# Sheet1_MCU.net
KiCad netlist of a schematic drawn in Altium Designer
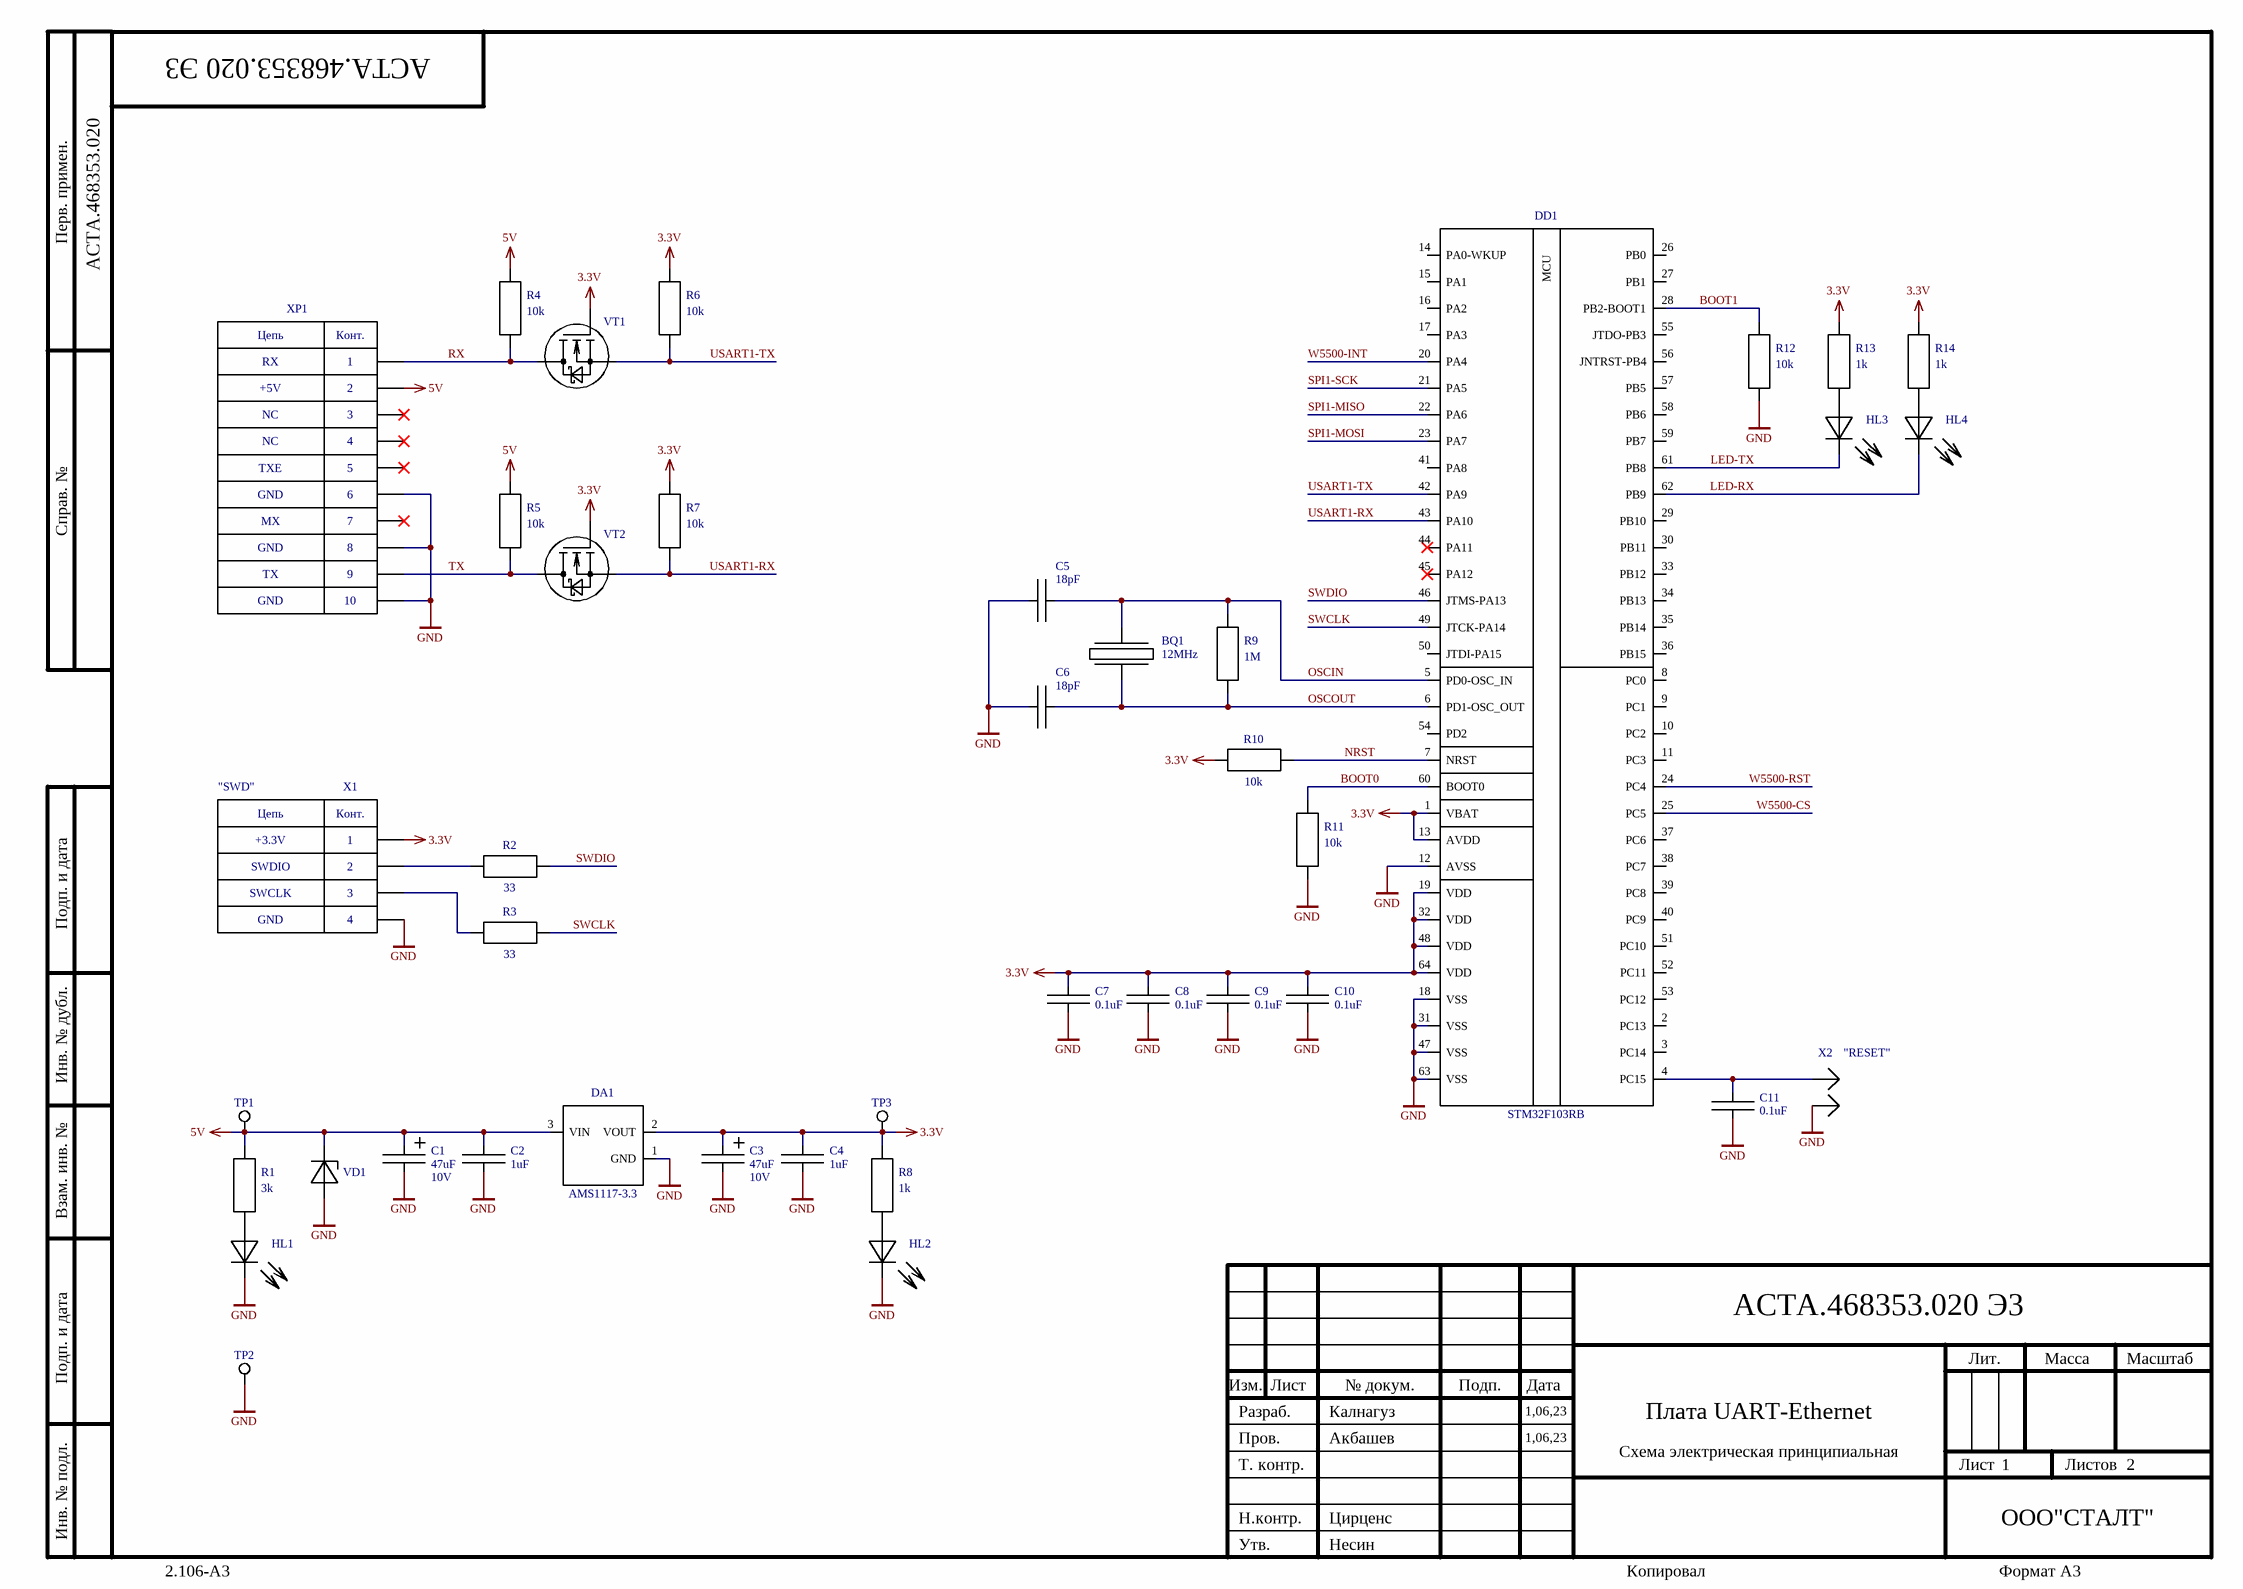
[diagram p0: Sheet1_MCU.SchDoc]

(export (version "E")
  (design (tool "Eeschema 10.0.6"))
  (components
    (comp (ref "BQ1")
      (value "12MHz")
      (footprint "HT-49S")
      (fields (field (name "Comment") "HT-49S_Rated"))
      (libsource (lib "Resonators") (part "HT-49S_Rated"))
    )
    (comp (ref "C1")
      (value "47uF")
      (footprint "CaseB_TantalumCap")
      (fields (field (name "VOLTAGE") "10V") (field (name "Comment") "CaseB_TantalumCap"))
      (libsource (lib "Tantalum_Capacitors") (part "CaseB_TantalumCap"))
    )
    (comp (ref "C2")
      (value "1uF")
      (footprint "CAP0805")
      (fields (field (name "Comment") "CAP0805_Rated"))
      (libsource (lib "Ceramic_Capacitors") (part "CAP0805_Rated"))
    )
    (comp (ref "C3")
      (value "47uF")
      (footprint "CaseB_TantalumCap")
      (fields (field (name "VOLTAGE") "10V") (field (name "Comment") "CaseB_TantalumCap"))
      (libsource (lib "Tantalum_Capacitors") (part "CaseB_TantalumCap"))
    )
    (comp (ref "C4")
      (value "1uF")
      (footprint "CAP0805")
      (fields (field (name "Comment") "CAP0805_Rated"))
      (libsource (lib "Ceramic_Capacitors") (part "CAP0805_Rated"))
    )
    (comp (ref "C5")
      (value "18pF")
      (footprint "CAP0805")
      (fields (field (name "Comment") "CAP0805_Rated"))
      (libsource (lib "Ceramic_Capacitors") (part "CAP0805_Rated"))
    )
    (comp (ref "C6")
      (value "18pF")
      (footprint "CAP0805")
      (fields (field (name "Comment") "CAP0805_Rated"))
      (libsource (lib "Ceramic_Capacitors") (part "CAP0805_Rated"))
    )
    (comp (ref "C7")
      (value "0.1uF")
      (footprint "CAP0805")
      (fields (field (name "Comment") "CAP0805_Rated"))
      (libsource (lib "Ceramic_Capacitors") (part "CAP0805_Rated"))
    )
    (comp (ref "C8")
      (value "0.1uF")
      (footprint "CAP0805")
      (fields (field (name "Comment") "CAP0805_Rated"))
      (libsource (lib "Ceramic_Capacitors") (part "CAP0805_Rated"))
    )
    (comp (ref "C9")
      (value "0.1uF")
      (footprint "CAP0805")
      (fields (field (name "Comment") "CAP0805_Rated"))
      (libsource (lib "Ceramic_Capacitors") (part "CAP0805_Rated"))
    )
    (comp (ref "C10")
      (value "0.1uF")
      (footprint "CAP0805")
      (fields (field (name "Comment") "CAP0805_Rated"))
      (libsource (lib "Ceramic_Capacitors") (part "CAP0805_Rated"))
    )
    (comp (ref "C11")
      (value "0.1uF")
      (footprint "CAP0805")
      (fields (field (name "Comment") "CAP0805_Rated"))
      (libsource (lib "Ceramic_Capacitors") (part "CAP0805_Rated"))
    )
    (comp (ref "DA1")
      (value "AMS1117-3.3")
      (footprint "SOT-223")
      (description "Fixed Voltage 3.3V 1A Low Dropout Voltage Regulator")
      (libsource (lib "Power_Management_ICs") (part "AMS1117-3.3"))
    )
    (comp (ref "DD1")
      (value "STM32F103RB")
      (footprint "LQFP-64")
      (description "ARM Cortex-M3 MCU")
      (libsource (lib "MCU") (part "STM32F103RB"))
    )
    (comp (ref "HL1")
      (value "KPTD-3216MGC")
      (footprint "KPTD-3216 Green")
      (description "3.2x1.6mm SMD LED Mega Green")
      (libsource (lib "LEDs_SMD") (part "KPTD-3216MGC"))
    )
    (comp (ref "HL2")
      (value "KPTD-3216MGC")
      (footprint "KPTD-3216 Green")
      (description "3.2x1.6mm SMD LED Mega Green")
      (libsource (lib "LEDs_SMD") (part "KPTD-3216MGC"))
    )
    (comp (ref "HL3")
      (value "KPTD-3216MGC")
      (footprint "KPTD-3216 Green")
      (description "3.2x1.6mm SMD LED Mega Green")
      (libsource (lib "LEDs_SMD") (part "KPTD-3216MGC"))
    )
    (comp (ref "HL4")
      (value "KPTD-3216SYC")
      (footprint "KPTD-3216 Yellow")
      (description "3.2x1.6mm SMD LED Super Bright Yellow")
      (libsource (lib "LEDs_SMD") (part "KPTD-3216SYC"))
    )
    (comp (ref "R1")
      (value "3k")
      (footprint "RES0805")
      (fields (field (name "TOLERANCE") "5%") (field (name "Comment") "RES0805_Rated"))
      (libsource (lib "Resistors") (part "RES0805_Rated"))
    )
    (comp (ref "R2")
      (value "33")
      (footprint "RES0805")
      (fields (field (name "TOLERANCE") "5%") (field (name "Comment") "RES0805_Rated"))
      (libsource (lib "") (part "RES0805_Rated_1"))
    )
    (comp (ref "R3")
      (value "33")
      (footprint "RES0805")
      (fields (field (name "TOLERANCE") "5%") (field (name "Comment") "RES0805_Rated"))
      (libsource (lib "") (part "RES0805_Rated_1"))
    )
    (comp (ref "R4")
      (value "10k")
      (footprint "RES0805")
      (fields (field (name "TOLERANCE") "5%") (field (name "Comment") "RES0805_Rated"))
      (libsource (lib "Resistors") (part "RES0805_Rated"))
    )
    (comp (ref "R5")
      (value "10k")
      (footprint "RES0805")
      (fields (field (name "TOLERANCE") "5%") (field (name "Comment") "RES0805_Rated"))
      (libsource (lib "Resistors") (part "RES0805_Rated"))
    )
    (comp (ref "R6")
      (value "10k")
      (footprint "RES0805")
      (fields (field (name "TOLERANCE") "5%") (field (name "Comment") "RES0805_Rated"))
      (libsource (lib "Resistors") (part "RES0805_Rated"))
    )
    (comp (ref "R7")
      (value "10k")
      (footprint "RES0805")
      (fields (field (name "TOLERANCE") "5%") (field (name "Comment") "RES0805_Rated"))
      (libsource (lib "Resistors") (part "RES0805_Rated"))
    )
    (comp (ref "R8")
      (value "1k")
      (footprint "RES0805")
      (fields (field (name "TOLERANCE") "5%") (field (name "Comment") "RES0805_Rated"))
      (libsource (lib "Resistors") (part "RES0805_Rated"))
    )
    (comp (ref "R9")
      (value "1M")
      (footprint "RES0805")
      (fields (field (name "TOLERANCE") "5%") (field (name "Comment") "RES0805_Rated"))
      (libsource (lib "Resistors") (part "RES0805_Rated"))
    )
    (comp (ref "R10")
      (value "10k")
      (footprint "RES0805")
      (fields (field (name "TOLERANCE") "5%") (field (name "Comment") "RES0805_Rated"))
      (libsource (lib "") (part "RES0805_Rated_1"))
    )
    (comp (ref "R11")
      (value "10k")
      (footprint "RES0805")
      (fields (field (name "TOLERANCE") "5%") (field (name "Comment") "RES0805_Rated"))
      (libsource (lib "Resistors") (part "RES0805_Rated"))
    )
    (comp (ref "R12")
      (value "10k")
      (footprint "RES0805")
      (fields (field (name "TOLERANCE") "5%") (field (name "Comment") "RES0805_Rated"))
      (libsource (lib "Resistors") (part "RES0805_Rated"))
    )
    (comp (ref "R13")
      (value "1k")
      (footprint "RES0805")
      (fields (field (name "TOLERANCE") "5%") (field (name "Comment") "RES0805_Rated"))
      (libsource (lib "Resistors") (part "RES0805_Rated"))
    )
    (comp (ref "R14")
      (value "1k")
      (footprint "RES0805")
      (fields (field (name "TOLERANCE") "5%") (field (name "Comment") "RES0805_Rated"))
      (libsource (lib "Resistors") (part "RES0805_Rated"))
    )
    (comp (ref "TP1")
      (value "TestPad")
      (footprint "PAD-TH-OCT1x1-0.5")
      (description "TestPoint on PCB")
      (libsource (lib "Connectors") (part "TestPad"))
    )
    (comp (ref "TP2")
      (value "TestPad")
      (footprint "PAD-TH-OCT1x1-0.5")
      (description "TestPoint on PCB")
      (libsource (lib "Connectors") (part "TestPad"))
    )
    (comp (ref "TP3")
      (value "TestPad")
      (footprint "PAD-TH-OCT1x1-0.5")
      (description "TestPoint on PCB")
      (libsource (lib "Connectors") (part "TestPad"))
    )
    (comp (ref "VD1")
      (value "SMAJ5.0A")
      (footprint "SMA (DO-214AC)")
      (description "5Vr 400W 43.5A UniDirectional TVS")
      (libsource (lib "TVS_Diodes") (part "SMAJ5.0A"))
    )
    (comp (ref "VT1")
      (value "BSS138")
      (footprint "SOT-23")
      (description "Small Signal N-Channel MOSFET 50V 220mA")
      (libsource (lib "MOSFETs") (part "BSS138"))
    )
    (comp (ref "VT2")
      (value "BSS138")
      (footprint "SOT-23")
      (description "Small Signal N-Channel MOSFET 50V 220mA")
      (libsource (lib "MOSFETs") (part "BSS138"))
    )
    (comp (ref "X1")
      (value "PBS-4")
      (footprint "PBS-4")
      (description "Female Header Pitch 2.54mm")
      (fields
        (field (name "CIRCUIT4") "GND")
        (field (name "CIRCUIT3") "SWCLK")
        (field (name "CIRCUIT1") "+3.3V")
        (field (name "CIRCUIT2") "SWDIO")
        (field (name "LABEL") "\"SWD\"")
      )
      (libsource (lib "Connectors") (part "PBS-4"))
    )
    (comp (ref "X2")
      (value "PLS-2")
      (footprint "PLS-2")
      (description "Pin Header Pitch 2.54mm")
      (fields (field (name "LABEL") "\"RESET\""))
      (libsource (lib "Connectors") (part "PLS-2"))
    )
    (comp (ref "XP1")
      (value "IDC-10MS")
      (footprint "IDC-10MS pad1.6x2.0")
      (description "Box Header Pitch 2.54mm")
      (fields
        (field (name "CIRCUIT7") "MX")
        (field (name "CIRCUIT8") "GND")
        (field (name "CIRCUIT9") "TX")
        (field (name "CIRCUIT10") "GND")
        (field (name "CIRCUIT6") "GND")
        (field (name "CIRCUIT4") "NC")
        (field (name "CIRCUIT5") "TXE")
        (field (name "CIRCUIT3") "NC")
        (field (name "CIRCUIT2") "+5V")
        (field (name "CIRCUIT1") "RX")
      )
      (libsource (lib "Connectors") (part "IDC-10MS"))
    )
  )
  (nets
    (net (code "1") (name "/BOOT0") (class "Default")
      (node (ref "DD1") (pin "60") (pinfunction "BOOT0_60") (pintype "power_in"))
      (node (ref "R11") (pin "2") (pinfunction "2_2") (pintype "passive"))
    )
    (net (code "2") (name "/BOOT1") (class "Default")
      (node (ref "DD1") (pin "28") (pinfunction "PB2-BOOT1_28") (pintype "bidirectional"))
      (node (ref "R12") (pin "2") (pinfunction "2_2") (pintype "passive"))
    )
    (net (code "3") (name "/LED-RX") (class "Default")
      (node (ref "DD1") (pin "62") (pinfunction "PB9_62") (pintype "bidirectional"))
      (node (ref "HL4") (pin "K") (pinfunction "K_K") (pintype "passive"))
    )
    (net (code "4") (name "/LED-TX") (class "Default")
      (node (ref "DD1") (pin "61") (pinfunction "PB8_61") (pintype "bidirectional"))
      (node (ref "HL3") (pin "K") (pinfunction "K_K") (pintype "passive"))
    )
    (net (code "5") (name "/NRST") (class "Default")
      (node (ref "DD1") (pin "7") (pinfunction "NRST_7") (pintype "bidirectional"))
      (node (ref "R10") (pin "2") (pinfunction "2_2") (pintype "passive"))
    )
    (net (code "6") (name "/OSCIN") (class "Default")
      (node (ref "BQ1") (pin "1") (pinfunction "1_1") (pintype "passive"))
      (node (ref "C5") (pin "2") (pinfunction "2_2") (pintype "passive"))
      (node (ref "DD1") (pin "5") (pinfunction "PD0-OSC_IN_5") (pintype "bidirectional"))
      (node (ref "R9") (pin "2") (pinfunction "2_2") (pintype "passive"))
    )
    (net (code "7") (name "/OSCOUT") (class "Default")
      (node (ref "BQ1") (pin "2") (pinfunction "2_2") (pintype "passive"))
      (node (ref "C6") (pin "2") (pinfunction "2_2") (pintype "passive"))
      (node (ref "DD1") (pin "6") (pinfunction "PD1-OSC_OUT_6") (pintype "bidirectional"))
      (node (ref "R9") (pin "1") (pinfunction "1_1") (pintype "passive"))
    )
    (net (code "8") (name "/RX") (class "Default")
      (node (ref "R4") (pin "1") (pinfunction "1_1") (pintype "passive"))
      (node (ref "VT1") (pin "2") (pinfunction "D_2") (pintype "passive"))
      (node (ref "XP1") (pin "1") (pinfunction "1_1") (pintype "passive"))
    )
    (net (code "9") (name "/SPI1-MISO") (class "Default")
      (node (ref "DD1") (pin "22") (pinfunction "PA6_22") (pintype "bidirectional"))
    )
    (net (code "10") (name "/SPI1-MOSI") (class "Default")
      (node (ref "DD1") (pin "23") (pinfunction "PA7_23") (pintype "bidirectional"))
    )
    (net (code "11") (name "/SPI1-SCK") (class "Default")
      (node (ref "DD1") (pin "21") (pinfunction "PA5_21") (pintype "bidirectional"))
    )
    (net (code "12") (name "/SWCLK") (class "Default")
      (node (ref "DD1") (pin "49") (pinfunction "JTCK-PA14_49") (pintype "bidirectional"))
      (node (ref "R3") (pin "2") (pinfunction "2_2") (pintype "passive"))
    )
    (net (code "13") (name "/SWDIO") (class "Default")
      (node (ref "DD1") (pin "46") (pinfunction "JTMS-PA13_46") (pintype "bidirectional"))
      (node (ref "R2") (pin "2") (pinfunction "2_2") (pintype "passive"))
    )
    (net (code "14") (name "/TX") (class "Default")
      (node (ref "R5") (pin "1") (pinfunction "1_1") (pintype "passive"))
      (node (ref "VT2") (pin "2") (pinfunction "D_2") (pintype "passive"))
      (node (ref "XP1") (pin "9") (pinfunction "9_9") (pintype "passive"))
    )
    (net (code "15") (name "/USART1-RX") (class "Default")
      (node (ref "DD1") (pin "43") (pinfunction "PA10_43") (pintype "bidirectional"))
      (node (ref "R7") (pin "1") (pinfunction "1_1") (pintype "passive"))
      (node (ref "VT2") (pin "3") (pinfunction "S_3") (pintype "passive"))
    )
    (net (code "16") (name "/USART1-TX") (class "Default")
      (node (ref "DD1") (pin "42") (pinfunction "PA9_42") (pintype "bidirectional"))
      (node (ref "R6") (pin "1") (pinfunction "1_1") (pintype "passive"))
      (node (ref "VT1") (pin "3") (pinfunction "S_3") (pintype "passive"))
    )
    (net (code "17") (name "/W5500-CS") (class "Default")
      (node (ref "DD1") (pin "25") (pinfunction "PC5_25") (pintype "bidirectional"))
    )
    (net (code "18") (name "/W5500-INT") (class "Default")
      (node (ref "DD1") (pin "20") (pinfunction "PA4_20") (pintype "bidirectional"))
    )
    (net (code "19") (name "/W5500-RST") (class "Default")
      (node (ref "DD1") (pin "24") (pinfunction "PC4_24") (pintype "bidirectional"))
    )
    (net (code "20") (name "3.3V") (class "Default")
      (node (ref "C10") (pin "1") (pinfunction "1_1") (pintype "passive"))
      (node (ref "C3") (pin "1") (pinfunction "+_1") (pintype "passive"))
      (node (ref "C4") (pin "1") (pinfunction "1_1") (pintype "passive"))
      (node (ref "C7") (pin "1") (pinfunction "1_1") (pintype "passive"))
      (node (ref "C8") (pin "1") (pinfunction "1_1") (pintype "passive"))
      (node (ref "C9") (pin "1") (pinfunction "1_1") (pintype "passive"))
      (node (ref "DA1") (pin "2") (pinfunction "VOUT_2") (pintype "power_in"))
      (node (ref "DD1") (pin "1") (pinfunction "VBAT_1") (pintype "power_in"))
      (node (ref "DD1") (pin "13") (pinfunction "AVDD_13") (pintype "power_in"))
      (node (ref "DD1") (pin "19") (pinfunction "VDD_19") (pintype "power_in"))
      (node (ref "DD1") (pin "32") (pinfunction "VDD_32") (pintype "power_in"))
      (node (ref "DD1") (pin "48") (pinfunction "VDD_48") (pintype "power_in"))
      (node (ref "DD1") (pin "64") (pinfunction "VDD_64") (pintype "power_in"))
      (node (ref "R10") (pin "1") (pinfunction "1_1") (pintype "passive"))
      (node (ref "R13") (pin "2") (pinfunction "2_2") (pintype "passive"))
      (node (ref "R14") (pin "2") (pinfunction "2_2") (pintype "passive"))
      (node (ref "R6") (pin "2") (pinfunction "2_2") (pintype "passive"))
      (node (ref "R7") (pin "2") (pinfunction "2_2") (pintype "passive"))
      (node (ref "R8") (pin "2") (pinfunction "2_2") (pintype "passive"))
      (node (ref "TP3") (pin "1") (pinfunction "1_1") (pintype "passive"))
      (node (ref "VT1") (pin "1") (pinfunction "G_1") (pintype "passive"))
      (node (ref "VT2") (pin "1") (pinfunction "G_1") (pintype "passive"))
      (node (ref "X1") (pin "1") (pinfunction "1_1") (pintype "passive"))
    )
    (net (code "21") (name "5V") (class "Default")
      (node (ref "C1") (pin "1") (pinfunction "+_1") (pintype "passive"))
      (node (ref "C2") (pin "1") (pinfunction "1_1") (pintype "passive"))
      (node (ref "DA1") (pin "3") (pinfunction "VIN_3") (pintype "power_in"))
      (node (ref "R1") (pin "2") (pinfunction "2_2") (pintype "passive"))
      (node (ref "R4") (pin "2") (pinfunction "2_2") (pintype "passive"))
      (node (ref "R5") (pin "2") (pinfunction "2_2") (pintype "passive"))
      (node (ref "TP1") (pin "1") (pinfunction "1_1") (pintype "passive"))
      (node (ref "VD1") (pin "K") (pinfunction "K_K") (pintype "passive"))
      (node (ref "XP1") (pin "2") (pinfunction "2_2") (pintype "passive"))
    )
    (net (code "22") (name "GND") (class "Default")
      (node (ref "C1") (pin "2") (pinfunction "-_2") (pintype "passive"))
      (node (ref "C10") (pin "2") (pinfunction "2_2") (pintype "passive"))
      (node (ref "C11") (pin "2") (pinfunction "2_2") (pintype "passive"))
      (node (ref "C2") (pin "2") (pinfunction "2_2") (pintype "passive"))
      (node (ref "C3") (pin "2") (pinfunction "-_2") (pintype "passive"))
      (node (ref "C4") (pin "2") (pinfunction "2_2") (pintype "passive"))
      (node (ref "C5") (pin "1") (pinfunction "1_1") (pintype "passive"))
      (node (ref "C6") (pin "1") (pinfunction "1_1") (pintype "passive"))
      (node (ref "C7") (pin "2") (pinfunction "2_2") (pintype "passive"))
      (node (ref "C8") (pin "2") (pinfunction "2_2") (pintype "passive"))
      (node (ref "C9") (pin "2") (pinfunction "2_2") (pintype "passive"))
      (node (ref "DA1") (pin "1") (pinfunction "GND_1") (pintype "power_in"))
      (node (ref "DD1") (pin "12") (pinfunction "AVSS_12") (pintype "power_in"))
      (node (ref "DD1") (pin "18") (pinfunction "VSS_18") (pintype "power_in"))
      (node (ref "DD1") (pin "31") (pinfunction "VSS_31") (pintype "power_in"))
      (node (ref "DD1") (pin "47") (pinfunction "VSS_47") (pintype "power_in"))
      (node (ref "DD1") (pin "63") (pinfunction "VSS_63") (pintype "power_in"))
      (node (ref "HL1") (pin "K") (pinfunction "K_K") (pintype "passive"))
      (node (ref "HL2") (pin "K") (pinfunction "K_K") (pintype "passive"))
      (node (ref "R11") (pin "1") (pinfunction "1_1") (pintype "passive"))
      (node (ref "R12") (pin "1") (pinfunction "1_1") (pintype "passive"))
      (node (ref "TP2") (pin "1") (pinfunction "1_1") (pintype "passive"))
      (node (ref "VD1") (pin "A") (pinfunction "A_A") (pintype "passive"))
      (node (ref "X1") (pin "4") (pinfunction "4_4") (pintype "passive"))
      (node (ref "X2") (pin "2") (pinfunction "2_2") (pintype "passive"))
      (node (ref "XP1") (pin "10") (pinfunction "10_10") (pintype "passive"))
      (node (ref "XP1") (pin "6") (pinfunction "6_6") (pintype "passive"))
      (node (ref "XP1") (pin "8") (pinfunction "8_8") (pintype "passive"))
    )
    (net (code "23") (name "Net-(DD1-PC15)") (class "Default")
      (node (ref "C11") (pin "1") (pinfunction "1_1") (pintype "passive"))
      (node (ref "DD1") (pin "4") (pinfunction "PC15_4") (pintype "bidirectional"))
      (node (ref "X2") (pin "1") (pinfunction "1_1") (pintype "passive"))
    )
    (net (code "24") (name "Net-(HL1-PadA)") (class "Default")
      (node (ref "HL1") (pin "A") (pinfunction "A_A") (pintype "passive"))
      (node (ref "R1") (pin "1") (pinfunction "1_1") (pintype "passive"))
    )
    (net (code "25") (name "Net-(HL2-PadA)") (class "Default")
      (node (ref "HL2") (pin "A") (pinfunction "A_A") (pintype "passive"))
      (node (ref "R8") (pin "1") (pinfunction "1_1") (pintype "passive"))
    )
    (net (code "26") (name "Net-(HL3-PadA)") (class "Default")
      (node (ref "HL3") (pin "A") (pinfunction "A_A") (pintype "passive"))
      (node (ref "R13") (pin "1") (pinfunction "1_1") (pintype "passive"))
    )
    (net (code "27") (name "Net-(HL4-PadA)") (class "Default")
      (node (ref "HL4") (pin "A") (pinfunction "A_A") (pintype "passive"))
      (node (ref "R14") (pin "1") (pinfunction "1_1") (pintype "passive"))
    )
    (net (code "28") (name "Net-(R2-Pad1)") (class "Default")
      (node (ref "R2") (pin "1") (pinfunction "1_1") (pintype "passive"))
      (node (ref "X1") (pin "2") (pinfunction "2_2") (pintype "passive"))
    )
    (net (code "29") (name "Net-(R3-Pad1)") (class "Default")
      (node (ref "R3") (pin "1") (pinfunction "1_1") (pintype "passive"))
      (node (ref "X1") (pin "3") (pinfunction "3_3") (pintype "passive"))
    )
    (net (code "30") (name "unconnected-(DD1-JNTRST-PB4-Pad56)") (class "Default")
      (node (ref "DD1") (pin "56") (pinfunction "JNTRST-PB4_56") (pintype "bidirectional"))
    )
    (net (code "31") (name "unconnected-(DD1-JTDI-PA15-Pad50)") (class "Default")
      (node (ref "DD1") (pin "50") (pinfunction "JTDI-PA15_50") (pintype "bidirectional"))
    )
    (net (code "32") (name "unconnected-(DD1-JTDO-PB3-Pad55)") (class "Default")
      (node (ref "DD1") (pin "55") (pinfunction "JTDO-PB3_55") (pintype "bidirectional"))
    )
    (net (code "33") (name "unconnected-(DD1-PA0-WKUP-Pad14)") (class "Default")
      (node (ref "DD1") (pin "14") (pinfunction "PA0-WKUP_14") (pintype "bidirectional"))
    )
    (net (code "34") (name "unconnected-(DD1-PA1-Pad15)") (class "Default")
      (node (ref "DD1") (pin "15") (pinfunction "PA1_15") (pintype "bidirectional"))
    )
    (net (code "35") (name "unconnected-(DD1-PA2-Pad16)") (class "Default")
      (node (ref "DD1") (pin "16") (pinfunction "PA2_16") (pintype "bidirectional"))
    )
    (net (code "36") (name "unconnected-(DD1-PA3-Pad17)") (class "Default")
      (node (ref "DD1") (pin "17") (pinfunction "PA3_17") (pintype "bidirectional"))
    )
    (net (code "37") (name "unconnected-(DD1-PA8-Pad41)") (class "Default")
      (node (ref "DD1") (pin "41") (pinfunction "PA8_41") (pintype "bidirectional"))
    )
    (net (code "38") (name "unconnected-(DD1-PA11-Pad44)") (class "Default")
      (node (ref "DD1") (pin "44") (pinfunction "PA11_44") (pintype "bidirectional+no_connect"))
    )
    (net (code "39") (name "unconnected-(DD1-PA12-Pad45)") (class "Default")
      (node (ref "DD1") (pin "45") (pinfunction "PA12_45") (pintype "bidirectional+no_connect"))
    )
    (net (code "40") (name "unconnected-(DD1-PB0-Pad26)") (class "Default")
      (node (ref "DD1") (pin "26") (pinfunction "PB0_26") (pintype "bidirectional"))
    )
    (net (code "41") (name "unconnected-(DD1-PB1-Pad27)") (class "Default")
      (node (ref "DD1") (pin "27") (pinfunction "PB1_27") (pintype "bidirectional"))
    )
    (net (code "42") (name "unconnected-(DD1-PB5-Pad57)") (class "Default")
      (node (ref "DD1") (pin "57") (pinfunction "PB5_57") (pintype "bidirectional"))
    )
    (net (code "43") (name "unconnected-(DD1-PB6-Pad58)") (class "Default")
      (node (ref "DD1") (pin "58") (pinfunction "PB6_58") (pintype "bidirectional"))
    )
    (net (code "44") (name "unconnected-(DD1-PB7-Pad59)") (class "Default")
      (node (ref "DD1") (pin "59") (pinfunction "PB7_59") (pintype "bidirectional"))
    )
    (net (code "45") (name "unconnected-(DD1-PB10-Pad29)") (class "Default")
      (node (ref "DD1") (pin "29") (pinfunction "PB10_29") (pintype "bidirectional"))
    )
    (net (code "46") (name "unconnected-(DD1-PB11-Pad30)") (class "Default")
      (node (ref "DD1") (pin "30") (pinfunction "PB11_30") (pintype "bidirectional"))
    )
    (net (code "47") (name "unconnected-(DD1-PB12-Pad33)") (class "Default")
      (node (ref "DD1") (pin "33") (pinfunction "PB12_33") (pintype "bidirectional"))
    )
    (net (code "48") (name "unconnected-(DD1-PB13-Pad34)") (class "Default")
      (node (ref "DD1") (pin "34") (pinfunction "PB13_34") (pintype "bidirectional"))
    )
    (net (code "49") (name "unconnected-(DD1-PB14-Pad35)") (class "Default")
      (node (ref "DD1") (pin "35") (pinfunction "PB14_35") (pintype "bidirectional"))
    )
    (net (code "50") (name "unconnected-(DD1-PB15-Pad36)") (class "Default")
      (node (ref "DD1") (pin "36") (pinfunction "PB15_36") (pintype "bidirectional"))
    )
    (net (code "51") (name "unconnected-(DD1-PC0-Pad8)") (class "Default")
      (node (ref "DD1") (pin "8") (pinfunction "PC0_8") (pintype "bidirectional"))
    )
    (net (code "52") (name "unconnected-(DD1-PC1-Pad9)") (class "Default")
      (node (ref "DD1") (pin "9") (pinfunction "PC1_9") (pintype "bidirectional"))
    )
    (net (code "53") (name "unconnected-(DD1-PC2-Pad10)") (class "Default")
      (node (ref "DD1") (pin "10") (pinfunction "PC2_10") (pintype "bidirectional"))
    )
    (net (code "54") (name "unconnected-(DD1-PC3-Pad11)") (class "Default")
      (node (ref "DD1") (pin "11") (pinfunction "PC3_11") (pintype "bidirectional"))
    )
    (net (code "55") (name "unconnected-(DD1-PC6-Pad37)") (class "Default")
      (node (ref "DD1") (pin "37") (pinfunction "PC6_37") (pintype "bidirectional"))
    )
    (net (code "56") (name "unconnected-(DD1-PC7-Pad38)") (class "Default")
      (node (ref "DD1") (pin "38") (pinfunction "PC7_38") (pintype "bidirectional"))
    )
    (net (code "57") (name "unconnected-(DD1-PC8-Pad39)") (class "Default")
      (node (ref "DD1") (pin "39") (pinfunction "PC8_39") (pintype "bidirectional"))
    )
    (net (code "58") (name "unconnected-(DD1-PC9-Pad40)") (class "Default")
      (node (ref "DD1") (pin "40") (pinfunction "PC9_40") (pintype "bidirectional"))
    )
    (net (code "59") (name "unconnected-(DD1-PC10-Pad51)") (class "Default")
      (node (ref "DD1") (pin "51") (pinfunction "PC10_51") (pintype "bidirectional"))
    )
    (net (code "60") (name "unconnected-(DD1-PC11-Pad52)") (class "Default")
      (node (ref "DD1") (pin "52") (pinfunction "PC11_52") (pintype "bidirectional"))
    )
    (net (code "61") (name "unconnected-(DD1-PC12-Pad53)") (class "Default")
      (node (ref "DD1") (pin "53") (pinfunction "PC12_53") (pintype "bidirectional"))
    )
    (net (code "62") (name "unconnected-(DD1-PC13-Pad2)") (class "Default")
      (node (ref "DD1") (pin "2") (pinfunction "PC13_2") (pintype "bidirectional"))
    )
    (net (code "63") (name "unconnected-(DD1-PC14-Pad3)") (class "Default")
      (node (ref "DD1") (pin "3") (pinfunction "PC14_3") (pintype "bidirectional"))
    )
    (net (code "64") (name "unconnected-(DD1-PD2-Pad54)") (class "Default")
      (node (ref "DD1") (pin "54") (pinfunction "PD2_54") (pintype "bidirectional"))
    )
    (net (code "65") (name "unconnected-(XP1-Pad3)") (class "Default")
      (node (ref "XP1") (pin "3") (pinfunction "3_3") (pintype "passive+no_connect"))
    )
    (net (code "66") (name "unconnected-(XP1-Pad4)") (class "Default")
      (node (ref "XP1") (pin "4") (pinfunction "4_4") (pintype "passive+no_connect"))
    )
    (net (code "67") (name "unconnected-(XP1-Pad5)") (class "Default")
      (node (ref "XP1") (pin "5") (pinfunction "5_5") (pintype "passive+no_connect"))
    )
    (net (code "68") (name "unconnected-(XP1-Pad7)") (class "Default")
      (node (ref "XP1") (pin "7") (pinfunction "7_7") (pintype "passive+no_connect"))
    )
  )
)
